# TPT02rr.net
KiCad netlist of a schematic drawn in EAGLE
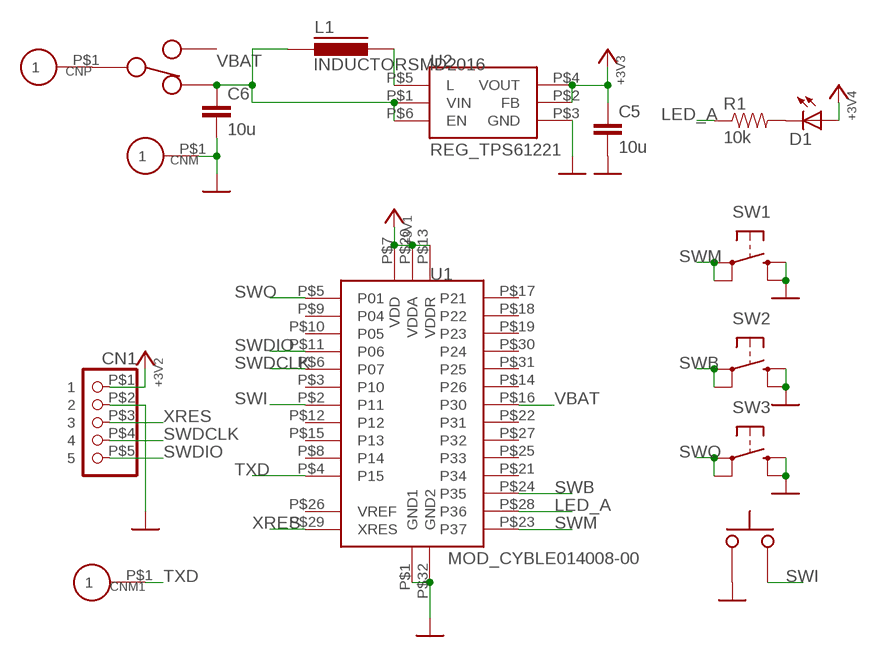
[diagram p0: schematic, sheet 1]

(export (version "E")
  (design (tool "Eeschema 10.0.6"))
  (components
    (comp (ref "C5")
      (value "10u")
      (footprint "eagle-import:0603")
      (libsource (lib "eagle-import") (part "CAP0603"))
    )
    (comp (ref "C6")
      (value "10u")
      (footprint "eagle-import:0603")
      (libsource (lib "eagle-import") (part "CAP0603"))
    )
    (comp (ref "CN1")
      (value "CON_PINHD-1X550MIL")
      (footprint "eagle-import:1X5_50MIL")
      (libsource (lib "eagle-import") (part "CON_PINHD-1X550MIL"))
    )
    (comp (ref "CNM")
      (value "CON_P01SMD1MM")
      (footprint "eagle-import:PAD_SMD1MM")
      (libsource (lib "eagle-import") (part "CON_P01SMD1MM"))
    )
    (comp (ref "CNM1")
      (value "CON_P01SMD1MM")
      (footprint "eagle-import:PAD_SMD1MM")
      (libsource (lib "eagle-import") (part "CON_P01SMD1MM"))
    )
    (comp (ref "CNP")
      (value "CON_P01SMD1MM")
      (footprint "eagle-import:PAD_SMD1MM")
      (libsource (lib "eagle-import") (part "CON_P01SMD1MM"))
    )
    (comp (ref "D1")
      (value "LED0603")
      (footprint "eagle-import:SPARKFUN_LED-0603")
      (libsource (lib "eagle-import") (part "LED0603"))
    )
    (comp (ref "L1")
      (value "INDUCTORSMD2016")
      (footprint "eagle-import:2016")
      (libsource (lib "eagle-import") (part "INDUCTORSMD2016"))
    )
    (comp (ref "R1")
      (value "10k")
      (footprint "eagle-import:0603")
      (libsource (lib "eagle-import") (part "RES0603"))
    )
    (comp (ref "SW1")
      (value "SW_TACTEVQP2")
      (footprint "eagle-import:SW_EVQP2")
      (libsource (lib "eagle-import") (part "SW_TACTEVQP2"))
    )
    (comp (ref "SW2")
      (value "SW_TACTEVQPLBA08")
      (footprint "eagle-import:SW_EVQPLBA08")
      (libsource (lib "eagle-import") (part "SW_TACTEVQPLBA08"))
    )
    (comp (ref "SW3")
      (value "SW_TACTEVQPLBA08")
      (footprint "eagle-import:SW_EVQPLBA08")
      (libsource (lib "eagle-import") (part "SW_TACTEVQPLBA08"))
    )
    (comp (ref "SW4")
      (value "SW_SLIDECUS12B")
      (footprint "eagle-import:SW_CUS-12B")
      (libsource (lib "eagle-import") (part "SW_SLIDECUS12B"))
    )
    (comp (ref "SW5")
      (value "SW_TACT2PB3U3000")
      (footprint "eagle-import:SW_B3U-3000P")
      (libsource (lib "eagle-import") (part "SW_TACT2PB3U3000"))
    )
    (comp (ref "U1")
      (value "MOD_CYBLE014008-00")
      (footprint "eagle-import:MOD_CYBLE014008-00")
      (libsource (lib "eagle-import") (part "MOD_CYBLE014008-00"))
    )
    (comp (ref "U2")
      (value "REG_TPS61221")
      (footprint "eagle-import:SC70-6")
      (libsource (lib "eagle-import") (part "REG_TPS61221"))
    )
  )
  (nets
    (net (code "1") (name "/LED_A") (class "Default")
      (node (ref "R1") (pin "1") (pinfunction "1_1") (pintype "passive"))
      (node (ref "U1") (pin "P$28") (pinfunction "P36_P$28") (pintype "bidirectional"))
    )
    (net (code "2") (name "/P$3") (class "Default")
      (node (ref "SW4") (pin "P$3") (pinfunction "P$3_P$3") (pintype "power_in"))
    )
    (net (code "3") (name "/SWB") (class "Default")
      (node (ref "SW2") (pin "A1") (pinfunction "P_A1") (pintype "passive"))
      (node (ref "SW2") (pin "A2") (pinfunction "P1_A2") (pintype "passive"))
      (node (ref "U1") (pin "P$24") (pinfunction "P35_P$24") (pintype "bidirectional"))
    )
    (net (code "4") (name "/SWDCLK") (class "Default")
      (node (ref "CN1") (pin "P$4") (pinfunction "4_P$4") (pintype "passive"))
      (node (ref "U1") (pin "P$6") (pinfunction "P07_P$6") (pintype "bidirectional"))
    )
    (net (code "5") (name "/SWDIO") (class "Default")
      (node (ref "CN1") (pin "P$5") (pinfunction "5_P$5") (pintype "passive"))
      (node (ref "U1") (pin "P$11") (pinfunction "P06_P$11") (pintype "bidirectional"))
    )
    (net (code "6") (name "/SWI") (class "Default")
      (node (ref "SW5") (pin "P$1") (pinfunction "P$1_P$1") (pintype "passive"))
      (node (ref "U1") (pin "P$2") (pinfunction "P11_P$2") (pintype "bidirectional"))
    )
    (net (code "7") (name "/SWM") (class "Default")
      (node (ref "SW1") (pin "PA1") (pinfunction "P_PA1") (pintype "passive"))
      (node (ref "SW1") (pin "PA2") (pinfunction "P1_PA2") (pintype "passive"))
      (node (ref "U1") (pin "P$23") (pinfunction "P37_P$23") (pintype "bidirectional"))
    )
    (net (code "8") (name "/SWO") (class "Default")
      (node (ref "SW3") (pin "A1") (pinfunction "P_A1") (pintype "passive"))
      (node (ref "SW3") (pin "A2") (pinfunction "P1_A2") (pintype "passive"))
      (node (ref "U1") (pin "P$5") (pinfunction "P01_P$5") (pintype "bidirectional"))
    )
    (net (code "9") (name "/TXD") (class "Default")
      (node (ref "CNM1") (pin "P$1") (pinfunction "1_P$1") (pintype "bidirectional"))
      (node (ref "U1") (pin "P$4") (pinfunction "P15_P$4") (pintype "bidirectional"))
    )
    (net (code "10") (name "/VBAT") (class "Default")
      (node (ref "C6") (pin "1") (pinfunction "1_1") (pintype "passive"))
      (node (ref "L1") (pin "P$1") (pinfunction "1_P$1") (pintype "passive"))
      (node (ref "SW4") (pin "P$1") (pinfunction "P$1_P$1") (pintype "power_in"))
      (node (ref "U1") (pin "P$16") (pinfunction "P30_P$16") (pintype "bidirectional"))
      (node (ref "U2") (pin "P$1") (pinfunction "VIN_P$1") (pintype "bidirectional"))
      (node (ref "U2") (pin "P$6") (pinfunction "EN_P$6") (pintype "bidirectional"))
    )
    (net (code "11") (name "/XRES") (class "Default")
      (node (ref "CN1") (pin "P$3") (pinfunction "3_P$3") (pintype "passive"))
      (node (ref "U1") (pin "P$29") (pinfunction "XRES_P$29") (pintype "bidirectional"))
    )
    (net (code "12") (name "Net-(CNP-1)") (class "Default")
      (node (ref "CNP") (pin "P$1") (pinfunction "1_P$1") (pintype "bidirectional"))
      (node (ref "SW4") (pin "P$2") (pinfunction "P$2_P$2") (pintype "power_in"))
    )
    (net (code "13") (name "Net-(D1-PadC)") (class "Default")
      (node (ref "D1") (pin "C") (pinfunction "C_C") (pintype "passive"))
      (node (ref "R1") (pin "2") (pinfunction "2_2") (pintype "passive"))
    )
    (net (code "14") (name "Net-(L1-2)") (class "Default")
      (node (ref "L1") (pin "P$2") (pinfunction "2_P$2") (pintype "passive"))
      (node (ref "U2") (pin "P$5") (pinfunction "L_P$5") (pintype "bidirectional"))
    )
    (net (code "15") (name "POW_+3V3") (class "Default")
      (node (ref "C5") (pin "1") (pinfunction "1_1") (pintype "passive"))
      (node (ref "CN1") (pin "P$1") (pinfunction "1_P$1") (pintype "passive"))
      (node (ref "D1") (pin "A") (pinfunction "A_A") (pintype "passive"))
      (node (ref "U1") (pin "P$13") (pinfunction "VDDR_P$13") (pintype "bidirectional"))
      (node (ref "U1") (pin "P$20") (pinfunction "VDDA_P$20") (pintype "bidirectional"))
      (node (ref "U1") (pin "P$7") (pinfunction "VDD_P$7") (pintype "bidirectional"))
      (node (ref "U2") (pin "P$2") (pinfunction "FB_P$2") (pintype "bidirectional"))
      (node (ref "U2") (pin "P$4") (pinfunction "VOUT_P$4") (pintype "bidirectional"))
    )
    (net (code "16") (name "POW_GND") (class "Default")
      (node (ref "C5") (pin "2") (pinfunction "2_2") (pintype "passive"))
      (node (ref "C6") (pin "2") (pinfunction "2_2") (pintype "passive"))
      (node (ref "CN1") (pin "P$2") (pinfunction "2_P$2") (pintype "passive"))
      (node (ref "CNM") (pin "P$1") (pinfunction "1_P$1") (pintype "bidirectional"))
      (node (ref "SW1") (pin "PB1") (pinfunction "S_PB1") (pintype "passive"))
      (node (ref "SW1") (pin "PB2") (pinfunction "S1_PB2") (pintype "passive"))
      (node (ref "SW2") (pin "B1") (pinfunction "S_B1") (pintype "passive"))
      (node (ref "SW2") (pin "B2") (pinfunction "S1_B2") (pintype "passive"))
      (node (ref "SW3") (pin "B1") (pinfunction "S_B1") (pintype "passive"))
      (node (ref "SW3") (pin "B2") (pinfunction "S1_B2") (pintype "passive"))
      (node (ref "SW5") (pin "P$2") (pinfunction "P$2_P$2") (pintype "passive"))
      (node (ref "U1") (pin "P$1") (pinfunction "GND1_P$1") (pintype "bidirectional"))
      (node (ref "U1") (pin "P$32") (pinfunction "GND2_P$32") (pintype "bidirectional"))
      (node (ref "U2") (pin "P$3") (pinfunction "GND_P$3") (pintype "bidirectional"))
    )
    (net (code "17") (name "unconnected-(U1-P04-PadP$9)") (class "Default")
      (node (ref "U1") (pin "P$9") (pinfunction "P04_P$9") (pintype "bidirectional"))
    )
    (net (code "18") (name "unconnected-(U1-P05-PadP$10)") (class "Default")
      (node (ref "U1") (pin "P$10") (pinfunction "P05_P$10") (pintype "bidirectional"))
    )
    (net (code "19") (name "unconnected-(U1-P10-PadP$3)") (class "Default")
      (node (ref "U1") (pin "P$3") (pinfunction "P10_P$3") (pintype "bidirectional"))
    )
    (net (code "20") (name "unconnected-(U1-P12-PadP$12)") (class "Default")
      (node (ref "U1") (pin "P$12") (pinfunction "P12_P$12") (pintype "bidirectional"))
    )
    (net (code "21") (name "unconnected-(U1-P13-PadP$15)") (class "Default")
      (node (ref "U1") (pin "P$15") (pinfunction "P13_P$15") (pintype "bidirectional"))
    )
    (net (code "22") (name "unconnected-(U1-P14-PadP$8)") (class "Default")
      (node (ref "U1") (pin "P$8") (pinfunction "P14_P$8") (pintype "bidirectional"))
    )
    (net (code "23") (name "unconnected-(U1-P21-PadP$17)") (class "Default")
      (node (ref "U1") (pin "P$17") (pinfunction "P21_P$17") (pintype "bidirectional"))
    )
    (net (code "24") (name "unconnected-(U1-P22-PadP$18)") (class "Default")
      (node (ref "U1") (pin "P$18") (pinfunction "P22_P$18") (pintype "bidirectional"))
    )
    (net (code "25") (name "unconnected-(U1-P23-PadP$19)") (class "Default")
      (node (ref "U1") (pin "P$19") (pinfunction "P23_P$19") (pintype "bidirectional"))
    )
    (net (code "26") (name "unconnected-(U1-P24-PadP$30)") (class "Default")
      (node (ref "U1") (pin "P$30") (pinfunction "P24_P$30") (pintype "bidirectional"))
    )
    (net (code "27") (name "unconnected-(U1-P25-PadP$31)") (class "Default")
      (node (ref "U1") (pin "P$31") (pinfunction "P25_P$31") (pintype "bidirectional"))
    )
    (net (code "28") (name "unconnected-(U1-P26-PadP$14)") (class "Default")
      (node (ref "U1") (pin "P$14") (pinfunction "P26_P$14") (pintype "bidirectional"))
    )
    (net (code "29") (name "unconnected-(U1-P31-PadP$22)") (class "Default")
      (node (ref "U1") (pin "P$22") (pinfunction "P31_P$22") (pintype "bidirectional"))
    )
    (net (code "30") (name "unconnected-(U1-P32-PadP$27)") (class "Default")
      (node (ref "U1") (pin "P$27") (pinfunction "P32_P$27") (pintype "bidirectional"))
    )
    (net (code "31") (name "unconnected-(U1-P33-PadP$25)") (class "Default")
      (node (ref "U1") (pin "P$25") (pinfunction "P33_P$25") (pintype "bidirectional"))
    )
    (net (code "32") (name "unconnected-(U1-P34-PadP$21)") (class "Default")
      (node (ref "U1") (pin "P$21") (pinfunction "P34_P$21") (pintype "bidirectional"))
    )
    (net (code "33") (name "unconnected-(U1-VREF-PadP$26)") (class "Default")
      (node (ref "U1") (pin "P$26") (pinfunction "VREF_P$26") (pintype "bidirectional"))
    )
  )
)
